# Com.net
KiCad netlist of a schematic drawn in Altium Designer
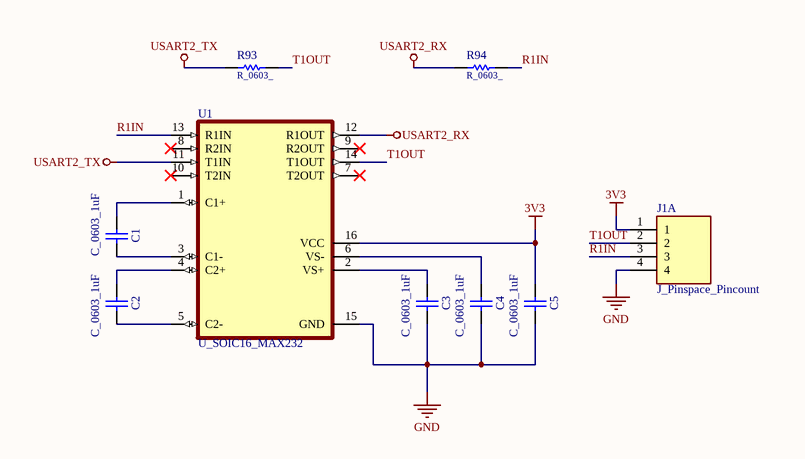
[diagram p0: Com.SchDoc]

(export (version "E")
  (design (tool "Eeschema 10.0.6"))
  (components
    (comp (ref "C1")
      (value "C_0603_1uF")
      (footprint "CAP 0603")
      (description "Capacitor")
      (fields (field (name "PUBLISHER") "Altium Limited"))
      (libsource (lib "HUE") (part "Cap"))
    )
    (comp (ref "C2")
      (value "C_0603_1uF")
      (footprint "CAP 0603")
      (description "Capacitor")
      (fields (field (name "PUBLISHER") "Altium Limited"))
      (libsource (lib "HUE") (part "Cap"))
    )
    (comp (ref "C3")
      (value "C_0603_1uF")
      (footprint "CAP 0603")
      (description "Capacitor")
      (fields (field (name "PUBLISHER") "Altium Limited"))
      (libsource (lib "HUE") (part "Cap"))
    )
    (comp (ref "C4")
      (value "C_0603_1uF")
      (footprint "CAP 0603")
      (description "Capacitor")
      (fields (field (name "PUBLISHER") "Altium Limited"))
      (libsource (lib "HUE") (part "Cap"))
    )
    (comp (ref "C5")
      (value "C_0603_1uF")
      (footprint "CAP 0603")
      (description "Capacitor")
      (fields (field (name "PUBLISHER") "Altium Limited"))
      (libsource (lib "HUE") (part "Cap"))
    )
    (comp (ref "J1")
      (value "J_Pinspace_Pincount")
      (footprint "4 Pin PCB TB 3.81")
      (fields (field (name "MP") "TBP02R1-381-04BE"))
      (libsource (lib "HUE") (part "4 Pin PCB Terminal Block"))
    )
    (comp (ref "R93")
      (value "R_0603_")
      (footprint "RES 0603")
      (description "Resistor")
      (fields (field (name "PUBLISHER") "Altium Limited"))
      (libsource (lib "HUE") (part "Res"))
    )
    (comp (ref "R94")
      (value "R_0603_")
      (footprint "RES 0603")
      (description "Resistor")
      (fields (field (name "PUBLISHER") "Altium Limited"))
      (libsource (lib "HUE") (part "Res"))
    )
    (comp (ref "U1")
      (value "U_SOIC16_MAX232")
      (footprint "SOIC16")
      (description "Dual EIA-232 driver and receiver 16-SOIC 0 to 70")
      (fields (field (name "MF") "Texas Instruments") (field (name "MP") "MAX232DW"))
      (libsource (lib "HUE") (part "MAX232DW"))
    )
  )
  (nets
    (net (code "1") (name "/R1IN") (class "Default")
      (node (ref "J1") (pin "3") (pinfunction "3_3") (pintype "passive"))
      (node (ref "R94") (pin "1") (pinfunction "1_1") (pintype "passive"))
      (node (ref "U1") (pin "13") (pinfunction "R1IN_13") (pintype "input"))
    )
    (net (code "2") (name "/T1OUT") (class "Default")
      (node (ref "J1") (pin "2") (pinfunction "2_2") (pintype "passive"))
      (node (ref "R93") (pin "1") (pinfunction "1_1") (pintype "passive"))
      (node (ref "U1") (pin "14") (pinfunction "T1OUT_14") (pintype "output"))
    )
    (net (code "3") (name "3V3") (class "Default")
      (node (ref "C5") (pin "2") (pinfunction "2_2") (pintype "passive"))
      (node (ref "J1") (pin "1") (pinfunction "1_1") (pintype "passive"))
      (node (ref "U1") (pin "16") (pinfunction "VCC_16") (pintype "power_in"))
    )
    (net (code "4") (name "GND") (class "Default")
      (node (ref "C3") (pin "1") (pinfunction "1_1") (pintype "passive"))
      (node (ref "C4") (pin "1") (pinfunction "1_1") (pintype "passive"))
      (node (ref "C5") (pin "1") (pinfunction "1_1") (pintype "passive"))
      (node (ref "J1") (pin "4") (pinfunction "4_4") (pintype "passive"))
      (node (ref "U1") (pin "15") (pinfunction "GND_15") (pintype "power_in"))
    )
    (net (code "5") (name "Net-(U1-C1+)") (class "Default")
      (node (ref "C1") (pin "2") (pinfunction "2_2") (pintype "passive"))
      (node (ref "U1") (pin "1") (pinfunction "C1+_1") (pintype "bidirectional"))
    )
    (net (code "6") (name "Net-(U1-C1-)") (class "Default")
      (node (ref "C1") (pin "1") (pinfunction "1_1") (pintype "passive"))
      (node (ref "U1") (pin "3") (pinfunction "C1-_3") (pintype "bidirectional"))
    )
    (net (code "7") (name "Net-(U1-C2+)") (class "Default")
      (node (ref "C2") (pin "2") (pinfunction "2_2") (pintype "passive"))
      (node (ref "U1") (pin "4") (pinfunction "C2+_4") (pintype "bidirectional"))
    )
    (net (code "8") (name "Net-(U1-C2-)") (class "Default")
      (node (ref "C2") (pin "1") (pinfunction "1_1") (pintype "passive"))
      (node (ref "U1") (pin "5") (pinfunction "C2-_5") (pintype "bidirectional"))
    )
    (net (code "9") (name "Net-(U1-VS+)") (class "Default")
      (node (ref "C3") (pin "2") (pinfunction "2_2") (pintype "passive"))
      (node (ref "U1") (pin "2") (pinfunction "VS+_2") (pintype "power_in"))
    )
    (net (code "10") (name "Net-(U1-VS-)") (class "Default")
      (node (ref "C4") (pin "2") (pinfunction "2_2") (pintype "passive"))
      (node (ref "U1") (pin "6") (pinfunction "VS-_6") (pintype "power_in"))
    )
    (net (code "11") (name "USART2_RX") (class "Default")
      (node (ref "R94") (pin "2") (pinfunction "2_2") (pintype "passive"))
      (node (ref "U1") (pin "12") (pinfunction "R1OUT_12") (pintype "output"))
    )
    (net (code "12") (name "USART2_TX") (class "Default")
      (node (ref "R93") (pin "2") (pinfunction "2_2") (pintype "passive"))
      (node (ref "U1") (pin "11") (pinfunction "T1IN_11") (pintype "input"))
    )
    (net (code "13") (name "unconnected-(U1-R2IN-Pad8)") (class "Default")
      (node (ref "U1") (pin "8") (pinfunction "R2IN_8") (pintype "input+no_connect"))
    )
    (net (code "14") (name "unconnected-(U1-R2OUT-Pad9)") (class "Default")
      (node (ref "U1") (pin "9") (pinfunction "R2OUT_9") (pintype "output+no_connect"))
    )
    (net (code "15") (name "unconnected-(U1-T2IN-Pad10)") (class "Default")
      (node (ref "U1") (pin "10") (pinfunction "T2IN_10") (pintype "input+no_connect"))
    )
    (net (code "16") (name "unconnected-(U1-T2OUT-Pad7)") (class "Default")
      (node (ref "U1") (pin "7") (pinfunction "T2OUT_7") (pintype "output+no_connect"))
    )
  )
)
